# Heater.net
KiCad netlist of a schematic drawn in Altium Designer
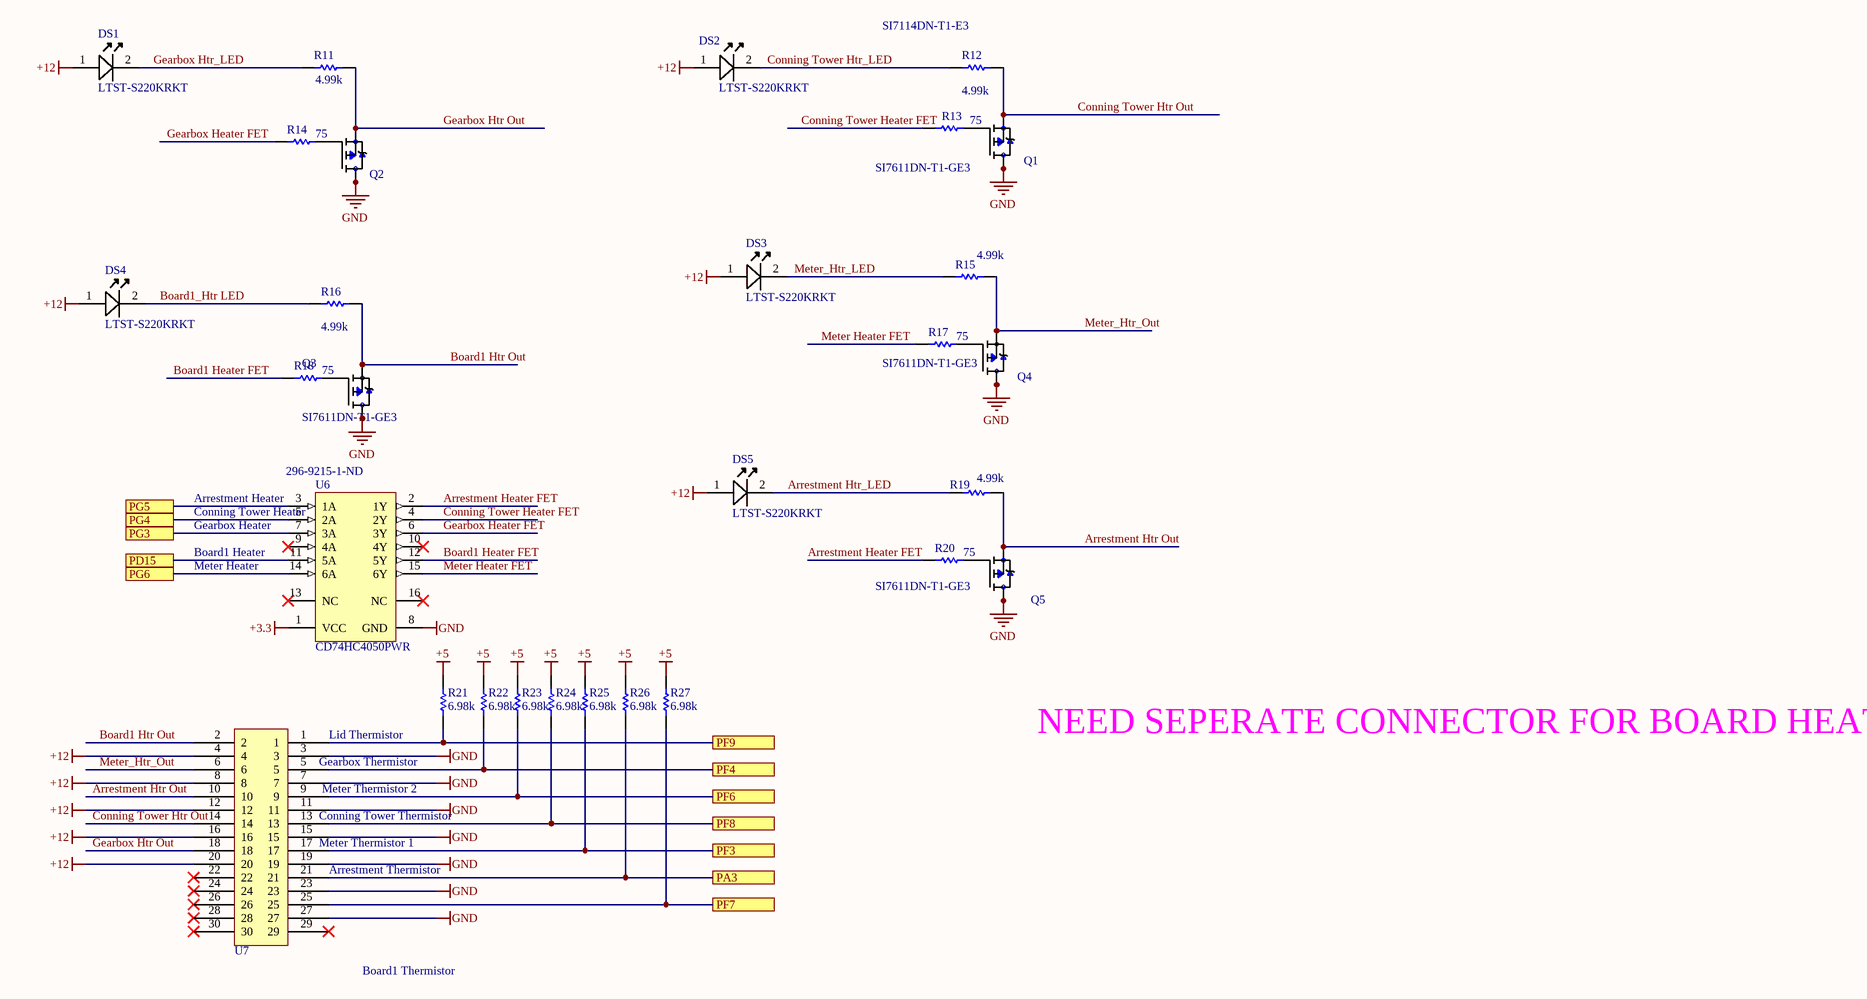
[diagram p0: Heater.SchDoc]

(export (version "E")
  (design (tool "Eeschema 10.0.6"))
  (components
    (comp (ref "DS1")
      (value "Visible Name Value Type    False Description Lite-On LTST-S220KRKT Red LED, 631 nm 2012 (0805) Side View, Rectangle Lens SMD package STRING")
      (footprint "0805C_L")
      (fields
        (field (name "MANUFACTURER") "Vishay / Lite-On")
        (field (name "MANUFACTURER PART NUMBER") "LTST-S220KRKT")
      )
      (libsource (lib "*") (part "LED A/K"))
    )
    (comp (ref "DS2")
      (value "Visible Name Value Type    False Description Lite-On LTST-S220KRKT Red LED, 631 nm 2012 (0805) Side View, Rectangle Lens SMD package STRING")
      (footprint "0805C_L")
      (fields
        (field (name "MANUFACTURER") "Vishay / Lite-On")
        (field (name "MANUFACTURER PART NUMBER") "LTST-S220KRKT")
      )
      (libsource (lib "*") (part "LED A/K"))
    )
    (comp (ref "DS3")
      (value "Visible Name Value Type    False Description Lite-On LTST-S220KRKT Red LED, 631 nm 2012 (0805) Side View, Rectangle Lens SMD package STRING")
      (footprint "0805C_L")
      (fields
        (field (name "MANUFACTURER") "Vishay / Lite-On")
        (field (name "MANUFACTURER PART NUMBER") "LTST-S220KRKT")
      )
      (libsource (lib "*") (part "LED A/K"))
    )
    (comp (ref "DS4")
      (value "Visible Name Value Type    False Description Lite-On LTST-S220KRKT Red LED, 631 nm 2012 (0805) Side View, Rectangle Lens SMD package STRING")
      (footprint "0805C_L")
      (fields
        (field (name "MANUFACTURER") "Vishay / Lite-On")
        (field (name "MANUFACTURER PART NUMBER") "LTST-S220KRKT")
      )
      (libsource (lib "*") (part "LED A/K"))
    )
    (comp (ref "DS5")
      (value "Visible Name Value Type    False Description Lite-On LTST-S220KRKT Red LED, 631 nm 2012 (0805) Side View, Rectangle Lens SMD package STRING")
      (footprint "0805C_L")
      (fields
        (field (name "MANUFACTURER") "Vishay / Lite-On")
        (field (name "MANUFACTURER PART NUMBER") "LTST-S220KRKT")
      )
      (libsource (lib "*") (part "LED A/K"))
    )
    (comp (ref "Q1")
      (value "SI7611DN-T1-GE3")
      (footprint "*VISHAY_SIS468DN-T1-GE3")
      (description "P-Channel 40 V 0.025 Ohm 39 W Surface Mount Power Mosfet - PowerPAK-1212-8")
      (fields
        (field (name "DIGI-KEY_PART_NUMBER") "SI7611DN-T1-GE3CT-ND")
        (field (name "MF") "Vishay Siliconix")
      )
      (libsource (lib "SI7611DN-T1-GE3") (part "SI7611DN-T1-GE3"))
    )
    (comp (ref "Q2")
      (value "SI7611DN-T1-GE3")
      (footprint "*VISHAY_SIS468DN-T1-GE3")
      (description "P-Channel 40 V 0.025 Ohm 39 W Surface Mount Power Mosfet - PowerPAK-1212-8")
      (fields
        (field (name "DIGI-KEY_PART_NUMBER") "SI7611DN-T1-GE3CT-ND")
        (field (name "MF") "Vishay Siliconix")
      )
      (libsource (lib "SI7611DN-T1-GE3") (part "SI7611DN-T1-GE3"))
    )
    (comp (ref "Q3")
      (value "SI7611DN-T1-GE3")
      (footprint "*VISHAY_SIS468DN-T1-GE3")
      (description "P-Channel 40 V 0.025 Ohm 39 W Surface Mount Power Mosfet - PowerPAK-1212-8")
      (fields
        (field (name "DIGI-KEY_PART_NUMBER") "SI7611DN-T1-GE3CT-ND")
        (field (name "MF") "Vishay Siliconix")
      )
      (libsource (lib "SI7611DN-T1-GE3") (part "SI7611DN-T1-GE3"))
    )
    (comp (ref "Q4")
      (value "SI7611DN-T1-GE3")
      (footprint "*VISHAY_SIS468DN-T1-GE3")
      (description "P-Channel 40 V 0.025 Ohm 39 W Surface Mount Power Mosfet - PowerPAK-1212-8")
      (fields
        (field (name "DIGI-KEY_PART_NUMBER") "SI7611DN-T1-GE3CT-ND")
        (field (name "MF") "Vishay Siliconix")
      )
      (libsource (lib "SI7611DN-T1-GE3") (part "SI7611DN-T1-GE3"))
    )
    (comp (ref "Q5")
      (value "SI7611DN-T1-GE3")
      (footprint "*VISHAY_SIS468DN-T1-GE3")
      (description "P-Channel 40 V 0.025 Ohm 39 W Surface Mount Power Mosfet - PowerPAK-1212-8")
      (fields
        (field (name "DIGI-KEY_PART_NUMBER") "SI7611DN-T1-GE3CT-ND")
        (field (name "MF") "Vishay Siliconix")
      )
      (libsource (lib "SI7611DN-T1-GE3") (part "SI7611DN-T1-GE3"))
    )
    (comp (ref "R11")
      (value "~")
      (footprint "RESC0805(2012)_L")
      (fields
        (field (name "MANUFACTURER") "Vishay Dale")
        (field (name "MANUFACTURER PART NUMBER") "CRCW08054K99FKEA")
        (field (name "RESISTANCE (OHMS)") "4.99k")
        (field (name "TOLERANCE") "±1%")
      )
      (libsource (lib "Altium Content Vault") (part "CMP-1013-00393-1"))
    )
    (comp (ref "R12")
      (value "~")
      (footprint "RESC0805(2012)_L")
      (fields
        (field (name "MANUFACTURER") "Vishay Dale")
        (field (name "MANUFACTURER PART NUMBER") "CRCW08054K99FKEA")
        (field (name "RESISTANCE (OHMS)") "4.99k")
        (field (name "TOLERANCE") "±1%")
      )
      (libsource (lib "Altium Content Vault") (part "CMP-1013-00393-1"))
    )
    (comp (ref "R13")
      (value "~")
      (footprint "RESC0805(2012)_L")
      (fields
        (field (name "MANUFACTURER") "Vishay Dale")
        (field (name "MANUFACTURER PART NUMBER") "CRCW080575R0FKEA")
        (field (name "RESISTANCE (OHMS)") "75")
        (field (name "TOLERANCE") "±1%")
      )
      (libsource (lib "Altium Content Vault") (part "CMP-1013-00393-1"))
    )
    (comp (ref "R14")
      (value "~")
      (footprint "RESC0805(2012)_L")
      (fields
        (field (name "MANUFACTURER") "Vishay Dale")
        (field (name "MANUFACTURER PART NUMBER") "CRCW080575R0FKEA")
        (field (name "RESISTANCE (OHMS)") "75")
        (field (name "TOLERANCE") "±1%")
      )
      (libsource (lib "Altium Content Vault") (part "CMP-1013-00393-1"))
    )
    (comp (ref "R15")
      (value "~")
      (footprint "RESC0805(2012)_L")
      (fields
        (field (name "MANUFACTURER") "Vishay Dale")
        (field (name "MANUFACTURER PART NUMBER") "CRCW08054K99FKEA")
        (field (name "RESISTANCE (OHMS)") "4.99k")
        (field (name "TOLERANCE") "±1%")
      )
      (libsource (lib "Altium Content Vault") (part "CMP-1013-00393-1"))
    )
    (comp (ref "R16")
      (value "~")
      (footprint "RESC0805(2012)_L")
      (fields
        (field (name "MANUFACTURER") "Vishay Dale")
        (field (name "MANUFACTURER PART NUMBER") "CRCW08054K99FKEA")
        (field (name "RESISTANCE (OHMS)") "4.99k")
        (field (name "TOLERANCE") "±1%")
      )
      (libsource (lib "Altium Content Vault") (part "CMP-1013-00393-1"))
    )
    (comp (ref "R17")
      (value "~")
      (footprint "RESC0805(2012)_L")
      (fields
        (field (name "MANUFACTURER") "Vishay Dale")
        (field (name "MANUFACTURER PART NUMBER") "CRCW080575R0FKEA")
        (field (name "RESISTANCE (OHMS)") "75")
        (field (name "TOLERANCE") "±1%")
      )
      (libsource (lib "Altium Content Vault") (part "CMP-1013-00393-1"))
    )
    (comp (ref "R18")
      (value "~")
      (footprint "RESC0805(2012)_L")
      (fields
        (field (name "MANUFACTURER") "Vishay Dale")
        (field (name "MANUFACTURER PART NUMBER") "CRCW080575R0FKEA")
        (field (name "RESISTANCE (OHMS)") "75")
        (field (name "TOLERANCE") "±1%")
      )
      (libsource (lib "Altium Content Vault") (part "CMP-1013-00393-1"))
    )
    (comp (ref "R19")
      (value "~")
      (footprint "RESC0805(2012)_L")
      (fields
        (field (name "MANUFACTURER") "Vishay Dale")
        (field (name "MANUFACTURER PART NUMBER") "CRCW08054K99FKEA")
        (field (name "RESISTANCE (OHMS)") "4.99k")
        (field (name "TOLERANCE") "±1%")
      )
      (libsource (lib "Altium Content Vault") (part "CMP-1013-00393-1"))
    )
    (comp (ref "R20")
      (value "~")
      (footprint "RESC0805(2012)_L")
      (fields
        (field (name "MANUFACTURER") "Vishay Dale")
        (field (name "MANUFACTURER PART NUMBER") "CRCW080575R0FKEA")
        (field (name "RESISTANCE (OHMS)") "75")
        (field (name "TOLERANCE") "±1%")
      )
      (libsource (lib "Altium Content Vault") (part "CMP-1013-00393-1"))
    )
    (comp (ref "R21")
      (value "6K98 1% 0805(2012)")
      (footprint "RESC0805(2012)_N")
      (description "6K98 0.125W 1% 0805 (2012 Metric)  SMD")
      (fields
        (field (name "MANUFACTURER") "Vishay Dale")
        (field (name "MANUFACTURER PART NUMBER") "CRCW08056K98FKEA")
        (field (name "RESISTANCE (OHMS)") "6.98k")
      )
      (libsource (lib "Altium Content Vault") (part "CMP-1013-00606-1"))
    )
    (comp (ref "R22")
      (value "6K98 1% 0805(2012)")
      (footprint "RESC0805(2012)_N")
      (description "6K98 0.125W 1% 0805 (2012 Metric)  SMD")
      (fields
        (field (name "MANUFACTURER") "Vishay Dale")
        (field (name "MANUFACTURER PART NUMBER") "CRCW08056K98FKEA")
        (field (name "RESISTANCE (OHMS)") "6.98k")
      )
      (libsource (lib "Altium Content Vault") (part "CMP-1013-00606-1"))
    )
    (comp (ref "R23")
      (value "6K98 1% 0805(2012)")
      (footprint "RESC0805(2012)_N")
      (description "6K98 0.125W 1% 0805 (2012 Metric)  SMD")
      (fields
        (field (name "MANUFACTURER") "Vishay Dale")
        (field (name "MANUFACTURER PART NUMBER") "CRCW08056K98FKEA")
        (field (name "RESISTANCE (OHMS)") "6.98k")
      )
      (libsource (lib "Altium Content Vault") (part "CMP-1013-00606-1"))
    )
    (comp (ref "R24")
      (value "6K98 1% 0805(2012)")
      (footprint "RESC0805(2012)_N")
      (description "6K98 0.125W 1% 0805 (2012 Metric)  SMD")
      (fields
        (field (name "MANUFACTURER") "Vishay Dale")
        (field (name "MANUFACTURER PART NUMBER") "CRCW08056K98FKEA")
        (field (name "RESISTANCE (OHMS)") "6.98k")
      )
      (libsource (lib "Altium Content Vault") (part "CMP-1013-00606-1"))
    )
    (comp (ref "R25")
      (value "6K98 1% 0805(2012)")
      (footprint "RESC0805(2012)_N")
      (description "6K98 0.125W 1% 0805 (2012 Metric)  SMD")
      (fields
        (field (name "MANUFACTURER") "Vishay Dale")
        (field (name "MANUFACTURER PART NUMBER") "CRCW08056K98FKEA")
        (field (name "RESISTANCE (OHMS)") "6.98k")
      )
      (libsource (lib "Altium Content Vault") (part "CMP-1013-00606-1"))
    )
    (comp (ref "R26")
      (value "6K98 1% 0805(2012)")
      (footprint "RESC0805(2012)_N")
      (description "6K98 0.125W 1% 0805 (2012 Metric)  SMD")
      (fields
        (field (name "MANUFACTURER") "Vishay Dale")
        (field (name "MANUFACTURER PART NUMBER") "CRCW08056K98FKEA")
        (field (name "RESISTANCE (OHMS)") "6.98k")
      )
      (libsource (lib "Altium Content Vault") (part "CMP-1013-00606-1"))
    )
    (comp (ref "R27")
      (value "6K98 1% 0805(2012)")
      (footprint "RESC0805(2012)_N")
      (description "6K98 0.125W 1% 0805 (2012 Metric)  SMD")
      (fields
        (field (name "MANUFACTURER") "Vishay Dale")
        (field (name "MANUFACTURER PART NUMBER") "CRCW08056K98FKEA")
        (field (name "RESISTANCE (OHMS)") "6.98k")
      )
      (libsource (lib "Altium Content Vault") (part "CMP-1013-00606-1"))
    )
    (comp (ref "U6")
      (value "CD74HC4050PWR")
      (footprint "PW0016A_N")
      (description "High Speed CMOS Logic Hex Non-Inverting Buffers, PW0016A, LARGE T&R")
      (fields
        (field (name "GENERIC PART NUMBER") "CD74HC4050")
        (field (name "MANUFACTURER") "Texas Instruments")
        (field (name "SUPPLIER PART NUMBER 1") "296-9215-1-ND")
      )
      (libsource (lib "Altium Content Vault") (part "TI-CDX4HC4050-16"))
    )
    (comp (ref "U7")
      (value "TFM-115-01-L-D-RE2-WT")
      (footprint "TFM-115-01-L-D-RE2-WT")
      (libsource (lib "ZLS_Schematic_lib") (part "TFM-115-01-L-D-RE2-WT"))
    )
  )
  (nets
    (net (code "1") (name "+3.3") (class "Default")
      (node (ref "U6") (pin "1") (pinfunction "VCC_1") (pintype "power_in"))
    )
    (net (code "2") (name "+5") (class "Default")
      (node (ref "R21") (pin "1") (pinfunction "1_1") (pintype "passive"))
      (node (ref "R22") (pin "2") (pinfunction "2_2") (pintype "passive"))
      (node (ref "R23") (pin "1") (pinfunction "1_1") (pintype "passive"))
      (node (ref "R24") (pin "2") (pinfunction "2_2") (pintype "passive"))
      (node (ref "R25") (pin "1") (pinfunction "1_1") (pintype "passive"))
      (node (ref "R26") (pin "2") (pinfunction "2_2") (pintype "passive"))
      (node (ref "R27") (pin "1") (pinfunction "1_1") (pintype "passive"))
    )
    (net (code "3") (name "+12") (class "Default")
      (node (ref "DS1") (pin "1") (pinfunction "A_1") (pintype "passive"))
      (node (ref "DS2") (pin "1") (pinfunction "A_1") (pintype "passive"))
      (node (ref "DS3") (pin "1") (pinfunction "A_1") (pintype "passive"))
      (node (ref "DS4") (pin "1") (pinfunction "A_1") (pintype "passive"))
      (node (ref "DS5") (pin "1") (pinfunction "A_1") (pintype "passive"))
      (node (ref "U7") (pin "12") (pinfunction "12_12") (pintype "passive"))
      (node (ref "U7") (pin "16") (pinfunction "16_16") (pintype "passive"))
      (node (ref "U7") (pin "20") (pinfunction "20_20") (pintype "passive"))
      (node (ref "U7") (pin "4") (pinfunction "4_4") (pintype "passive"))
      (node (ref "U7") (pin "8") (pinfunction "8_8") (pintype "passive"))
    )
    (net (code "4") (name "/Arrestment Heater FET") (class "Default")
      (node (ref "R20") (pin "1") (pinfunction "1_1") (pintype "passive"))
      (node (ref "U6") (pin "2") (pinfunction "1Y_2") (pintype "output"))
    )
    (net (code "5") (name "/Arrestment Htr Out") (class "Default")
      (node (ref "Q5") (pin "1") (pinfunction "S_1") (pintype "passive"))
      (node (ref "Q5") (pin "2") (pinfunction "S_2") (pintype "passive"))
      (node (ref "Q5") (pin "3") (pinfunction "S_3") (pintype "passive"))
      (node (ref "R19") (pin "2") (pinfunction "2_2") (pintype "passive"))
      (node (ref "U7") (pin "10") (pinfunction "10_10") (pintype "passive"))
    )
    (net (code "6") (name "/Arrestment Htr_LED") (class "Default")
      (node (ref "DS5") (pin "2") (pinfunction "K_2") (pintype "passive"))
      (node (ref "R19") (pin "1") (pinfunction "1_1") (pintype "passive"))
    )
    (net (code "7") (name "/Board1 Heater FET") (class "Default")
      (node (ref "R18") (pin "1") (pinfunction "1_1") (pintype "passive"))
      (node (ref "U6") (pin "12") (pinfunction "5Y_12") (pintype "output"))
    )
    (net (code "8") (name "/Board1 Htr Out") (class "Default")
      (node (ref "Q3") (pin "1") (pinfunction "S_1") (pintype "passive"))
      (node (ref "Q3") (pin "2") (pinfunction "S_2") (pintype "passive"))
      (node (ref "Q3") (pin "3") (pinfunction "S_3") (pintype "passive"))
      (node (ref "R16") (pin "1") (pinfunction "1_1") (pintype "passive"))
      (node (ref "U7") (pin "2") (pinfunction "2_2") (pintype "passive"))
    )
    (net (code "9") (name "/Board1_Htr LED") (class "Default")
      (node (ref "DS4") (pin "2") (pinfunction "K_2") (pintype "passive"))
      (node (ref "R16") (pin "2") (pinfunction "2_2") (pintype "passive"))
    )
    (net (code "10") (name "/Conning Tower Heater FET") (class "Default")
      (node (ref "R13") (pin "1") (pinfunction "1_1") (pintype "passive"))
      (node (ref "U6") (pin "4") (pinfunction "2Y_4") (pintype "output"))
    )
    (net (code "11") (name "/Conning Tower Htr Out") (class "Default")
      (node (ref "Q1") (pin "1") (pinfunction "S_1") (pintype "passive"))
      (node (ref "Q1") (pin "2") (pinfunction "S_2") (pintype "passive"))
      (node (ref "Q1") (pin "3") (pinfunction "S_3") (pintype "passive"))
      (node (ref "R12") (pin "1") (pinfunction "1_1") (pintype "passive"))
      (node (ref "U7") (pin "14") (pinfunction "14_14") (pintype "passive"))
    )
    (net (code "12") (name "/Conning Tower Htr_LED") (class "Default")
      (node (ref "DS2") (pin "2") (pinfunction "K_2") (pintype "passive"))
      (node (ref "R12") (pin "2") (pinfunction "2_2") (pintype "passive"))
    )
    (net (code "13") (name "/Gearbox Heater FET") (class "Default")
      (node (ref "R14") (pin "1") (pinfunction "1_1") (pintype "passive"))
      (node (ref "U6") (pin "6") (pinfunction "3Y_6") (pintype "output"))
    )
    (net (code "14") (name "/Gearbox Htr Out") (class "Default")
      (node (ref "Q2") (pin "1") (pinfunction "S_1") (pintype "passive"))
      (node (ref "Q2") (pin "2") (pinfunction "S_2") (pintype "passive"))
      (node (ref "Q2") (pin "3") (pinfunction "S_3") (pintype "passive"))
      (node (ref "R11") (pin "1") (pinfunction "1_1") (pintype "passive"))
      (node (ref "U7") (pin "18") (pinfunction "18_18") (pintype "passive"))
    )
    (net (code "15") (name "/Gearbox Htr_LED") (class "Default")
      (node (ref "DS1") (pin "2") (pinfunction "K_2") (pintype "passive"))
      (node (ref "R11") (pin "2") (pinfunction "2_2") (pintype "passive"))
    )
    (net (code "16") (name "/Meter Heater FET") (class "Default")
      (node (ref "R17") (pin "1") (pinfunction "1_1") (pintype "passive"))
      (node (ref "U6") (pin "15") (pinfunction "6Y_15") (pintype "output"))
    )
    (net (code "17") (name "/Meter_Htr_LED") (class "Default")
      (node (ref "DS3") (pin "2") (pinfunction "K_2") (pintype "passive"))
      (node (ref "R15") (pin "1") (pinfunction "1_1") (pintype "passive"))
    )
    (net (code "18") (name "/Meter_Htr_Out") (class "Default")
      (node (ref "Q4") (pin "1") (pinfunction "S_1") (pintype "passive"))
      (node (ref "Q4") (pin "2") (pinfunction "S_2") (pintype "passive"))
      (node (ref "Q4") (pin "3") (pinfunction "S_3") (pintype "passive"))
      (node (ref "R15") (pin "2") (pinfunction "2_2") (pintype "passive"))
      (node (ref "U7") (pin "6") (pinfunction "6_6") (pintype "passive"))
    )
    (net (code "19") (name "/PA3") (class "Default")
      (node (ref "R26") (pin "1") (pinfunction "1_1") (pintype "passive"))
      (node (ref "U7") (pin "21") (pinfunction "21_21") (pintype "passive"))
    )
    (net (code "20") (name "/PD15") (class "Default")
      (node (ref "U6") (pin "11") (pinfunction "5A_11") (pintype "input"))
    )
    (net (code "21") (name "/PF3") (class "Default")
      (node (ref "R25") (pin "2") (pinfunction "2_2") (pintype "passive"))
      (node (ref "U7") (pin "17") (pinfunction "17_17") (pintype "passive"))
    )
    (net (code "22") (name "/PF4") (class "Default")
      (node (ref "R22") (pin "1") (pinfunction "1_1") (pintype "passive"))
      (node (ref "U7") (pin "5") (pinfunction "5_5") (pintype "passive"))
    )
    (net (code "23") (name "/PF6") (class "Default")
      (node (ref "R23") (pin "2") (pinfunction "2_2") (pintype "passive"))
      (node (ref "U7") (pin "9") (pinfunction "9_9") (pintype "passive"))
    )
    (net (code "24") (name "/PF7") (class "Default")
      (node (ref "R27") (pin "2") (pinfunction "2_2") (pintype "passive"))
      (node (ref "U7") (pin "25") (pinfunction "25_25") (pintype "passive"))
    )
    (net (code "25") (name "/PF8") (class "Default")
      (node (ref "R24") (pin "1") (pinfunction "1_1") (pintype "passive"))
      (node (ref "U7") (pin "13") (pinfunction "13_13") (pintype "passive"))
    )
    (net (code "26") (name "/PF9") (class "Default")
      (node (ref "R21") (pin "2") (pinfunction "2_2") (pintype "passive"))
      (node (ref "U7") (pin "1") (pinfunction "1_1") (pintype "passive"))
    )
    (net (code "27") (name "/PG3") (class "Default")
      (node (ref "U6") (pin "7") (pinfunction "3A_7") (pintype "input"))
    )
    (net (code "28") (name "/PG4") (class "Default")
      (node (ref "U6") (pin "5") (pinfunction "2A_5") (pintype "input"))
    )
    (net (code "29") (name "/PG5") (class "Default")
      (node (ref "U6") (pin "3") (pinfunction "1A_3") (pintype "input"))
    )
    (net (code "30") (name "/PG6") (class "Default")
      (node (ref "U6") (pin "14") (pinfunction "6A_14") (pintype "input"))
    )
    (net (code "31") (name "GND") (class "Default")
      (node (ref "Q1") (pin "5") (pinfunction "D_5") (pintype "passive"))
      (node (ref "Q1") (pin "6") (pinfunction "D_6") (pintype "passive"))
      (node (ref "Q1") (pin "7") (pinfunction "D_7") (pintype "passive"))
      (node (ref "Q1") (pin "8") (pinfunction "D_8") (pintype "passive"))
      (node (ref "Q1") (pin "9") (pinfunction "D_9") (pintype "passive"))
      (node (ref "Q2") (pin "5") (pinfunction "D_5") (pintype "passive"))
      (node (ref "Q2") (pin "6") (pinfunction "D_6") (pintype "passive"))
      (node (ref "Q2") (pin "7") (pinfunction "D_7") (pintype "passive"))
      (node (ref "Q2") (pin "8") (pinfunction "D_8") (pintype "passive"))
      (node (ref "Q2") (pin "9") (pinfunction "D_9") (pintype "passive"))
      (node (ref "Q3") (pin "5") (pinfunction "D_5") (pintype "passive"))
      (node (ref "Q3") (pin "6") (pinfunction "D_6") (pintype "passive"))
      (node (ref "Q3") (pin "7") (pinfunction "D_7") (pintype "passive"))
      (node (ref "Q3") (pin "8") (pinfunction "D_8") (pintype "passive"))
      (node (ref "Q3") (pin "9") (pinfunction "D_9") (pintype "passive"))
      (node (ref "Q4") (pin "5") (pinfunction "D_5") (pintype "passive"))
      (node (ref "Q4") (pin "6") (pinfunction "D_6") (pintype "passive"))
      (node (ref "Q4") (pin "7") (pinfunction "D_7") (pintype "passive"))
      (node (ref "Q4") (pin "8") (pinfunction "D_8") (pintype "passive"))
      (node (ref "Q4") (pin "9") (pinfunction "D_9") (pintype "passive"))
      (node (ref "Q5") (pin "5") (pinfunction "D_5") (pintype "passive"))
      (node (ref "Q5") (pin "6") (pinfunction "D_6") (pintype "passive"))
      (node (ref "Q5") (pin "7") (pinfunction "D_7") (pintype "passive"))
      (node (ref "Q5") (pin "8") (pinfunction "D_8") (pintype "passive"))
      (node (ref "Q5") (pin "9") (pinfunction "D_9") (pintype "passive"))
      (node (ref "U6") (pin "8") (pinfunction "GND_8") (pintype "power_in"))
      (node (ref "U7") (pin "11") (pinfunction "11_11") (pintype "passive"))
      (node (ref "U7") (pin "15") (pinfunction "15_15") (pintype "passive"))
      (node (ref "U7") (pin "19") (pinfunction "19_19") (pintype "passive"))
      (node (ref "U7") (pin "23") (pinfunction "23_23") (pintype "passive"))
      (node (ref "U7") (pin "27") (pinfunction "27_27") (pintype "passive"))
      (node (ref "U7") (pin "3") (pinfunction "3_3") (pintype "passive"))
      (node (ref "U7") (pin "7") (pinfunction "7_7") (pintype "passive"))
    )
    (net (code "32") (name "Net-(Q1-G)") (class "Default")
      (node (ref "Q1") (pin "4") (pinfunction "G_4") (pintype "passive"))
      (node (ref "R13") (pin "2") (pinfunction "2_2") (pintype "passive"))
    )
    (net (code "33") (name "Net-(Q2-G)") (class "Default")
      (node (ref "Q2") (pin "4") (pinfunction "G_4") (pintype "passive"))
      (node (ref "R14") (pin "2") (pinfunction "2_2") (pintype "passive"))
    )
    (net (code "34") (name "Net-(Q3-G)") (class "Default")
      (node (ref "Q3") (pin "4") (pinfunction "G_4") (pintype "passive"))
      (node (ref "R18") (pin "2") (pinfunction "2_2") (pintype "passive"))
    )
    (net (code "35") (name "Net-(Q4-G)") (class "Default")
      (node (ref "Q4") (pin "4") (pinfunction "G_4") (pintype "passive"))
      (node (ref "R17") (pin "2") (pinfunction "2_2") (pintype "passive"))
    )
    (net (code "36") (name "Net-(Q5-G)") (class "Default")
      (node (ref "Q5") (pin "4") (pinfunction "G_4") (pintype "passive"))
      (node (ref "R20") (pin "2") (pinfunction "2_2") (pintype "passive"))
    )
    (net (code "37") (name "unconnected-(U6-4A-Pad9)") (class "Default")
      (node (ref "U6") (pin "9") (pinfunction "4A_9") (pintype "input+no_connect"))
    )
    (net (code "38") (name "unconnected-(U6-4Y-Pad10)") (class "Default")
      (node (ref "U6") (pin "10") (pinfunction "4Y_10") (pintype "output+no_connect"))
    )
    (net (code "39") (name "unconnected-(U6-NC-Pad13)") (class "Default")
      (node (ref "U6") (pin "13") (pinfunction "NC_13") (pintype "passive+no_connect"))
    )
    (net (code "40") (name "unconnected-(U6-NC-Pad16)") (class "Default")
      (node (ref "U6") (pin "16") (pinfunction "NC_16") (pintype "passive+no_connect"))
    )
    (net (code "41") (name "unconnected-(U7-Pad22)") (class "Default")
      (node (ref "U7") (pin "22") (pinfunction "22_22") (pintype "passive+no_connect"))
    )
    (net (code "42") (name "unconnected-(U7-Pad24)") (class "Default")
      (node (ref "U7") (pin "24") (pinfunction "24_24") (pintype "passive+no_connect"))
    )
    (net (code "43") (name "unconnected-(U7-Pad26)") (class "Default")
      (node (ref "U7") (pin "26") (pinfunction "26_26") (pintype "passive+no_connect"))
    )
    (net (code "44") (name "unconnected-(U7-Pad28)") (class "Default")
      (node (ref "U7") (pin "28") (pinfunction "28_28") (pintype "passive+no_connect"))
    )
    (net (code "45") (name "unconnected-(U7-Pad29)") (class "Default")
      (node (ref "U7") (pin "29") (pinfunction "29_29") (pintype "passive+no_connect"))
    )
    (net (code "46") (name "unconnected-(U7-Pad30)") (class "Default")
      (node (ref "U7") (pin "30") (pinfunction "30_30") (pintype "passive+no_connect"))
    )
  )
)
